# Power_Supply.net
KiCad netlist of a schematic drawn in Altium Designer
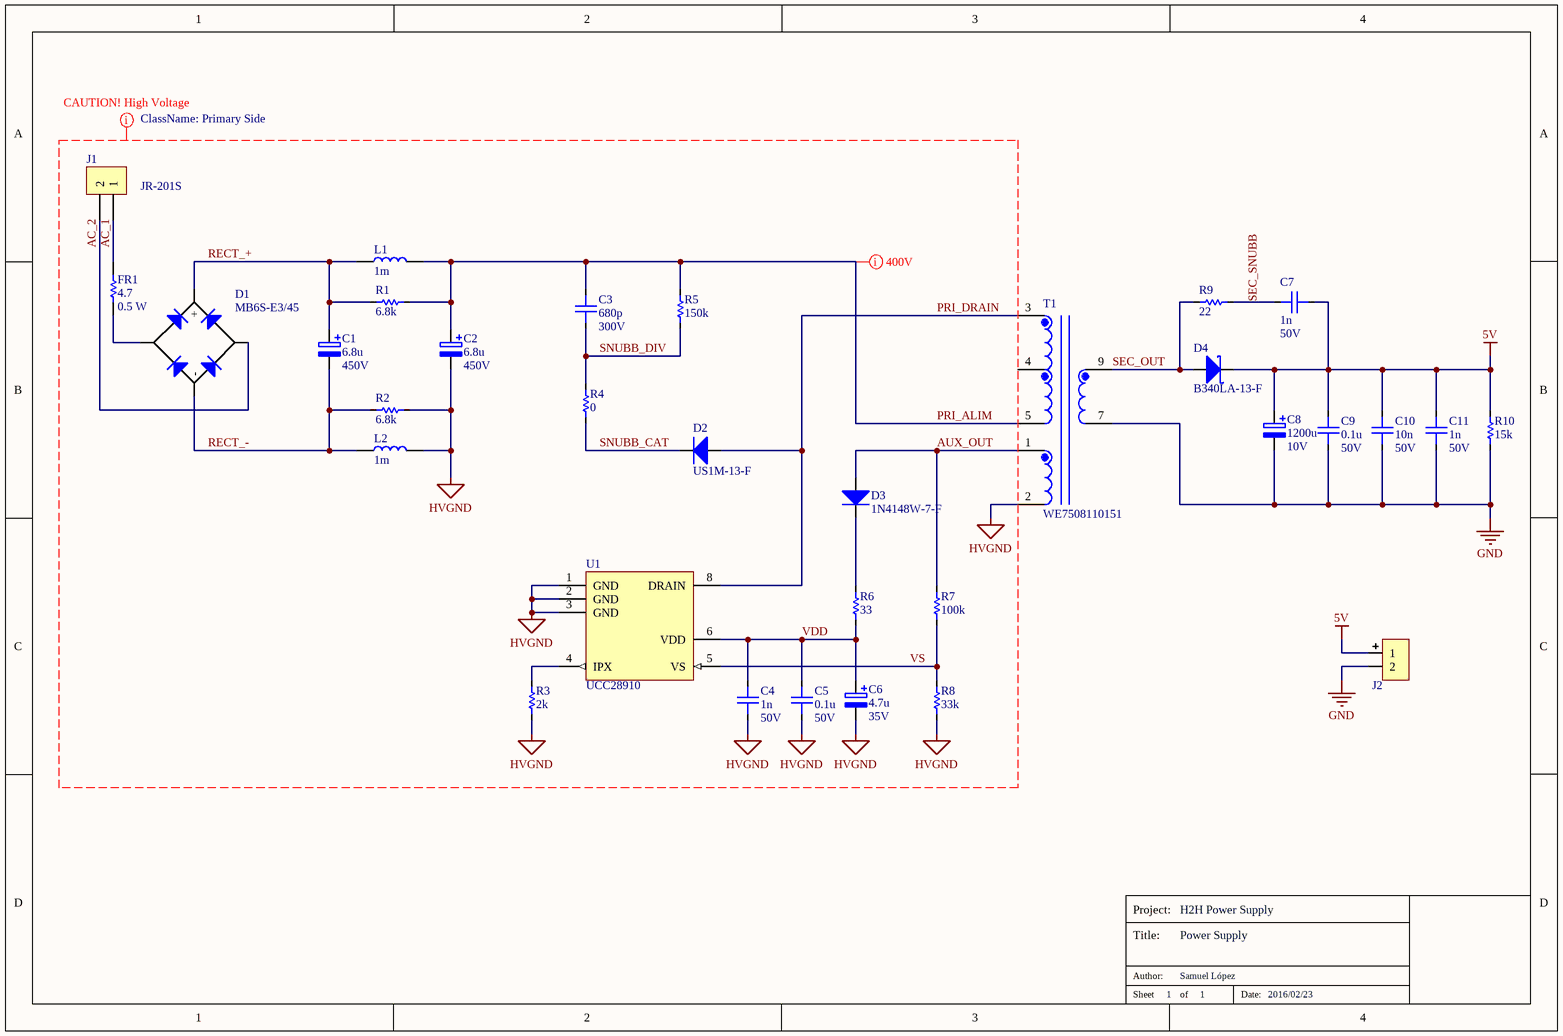
[diagram p0: Power Supply.SchDoc]

(export (version "E")
  (design (tool "Eeschema 10.0.6"))
  (components
    (comp (ref "C1")
      (value "6.8u")
      (footprint "450BXC6R8MEFC10X16")
      (description "Capacitor - Electrolytic Capacitor, 6.8 uF, 450 V, 20%, 10 mm")
      (fields (field (name "RATED VOLTAGE") "450V"))
      (libsource (lib "Supply") (part "450BXC6R8MEFC10X16"))
    )
    (comp (ref "C2")
      (value "6.8u")
      (footprint "450BXC6R8MEFC10X16")
      (description "Capacitor - Electrolytic Capacitor, 6.8 uF, 450 V, 20%, 10 mm")
      (fields (field (name "RATED VOLTAGE") "450V"))
      (libsource (lib "Supply") (part "450BXC6R8MEFC10X16"))
    )
    (comp (ref "C3")
      (value "680p")
      (footprint "C1206")
      (description "Capacitor")
      (fields (field (name "RATED VOLTAGE") "300V"))
      (libsource (lib "Misc") (part "Capacitor"))
    )
    (comp (ref "C4")
      (value "1n")
      (footprint "C1206")
      (description "Capacitor")
      (fields (field (name "RATED VOLTAGE") "50V"))
      (libsource (lib "Misc") (part "Capacitor"))
    )
    (comp (ref "C5")
      (value "0.1u")
      (footprint "C1206")
      (description "Capacitor")
      (fields (field (name "RATED VOLTAGE") "50V"))
      (libsource (lib "Misc") (part "Capacitor"))
    )
    (comp (ref "C6")
      (value "4.7u")
      (footprint "EXV475M035A9BAA")
      (description "Capacitor - Electrolytic Capacitor, SMD, 4.7 uF, 35 V, 4 mm")
      (fields (field (name "RATED VOLTAGE") "35V"))
      (libsource (lib "Supply") (part "EXV475M035A9BAA"))
    )
    (comp (ref "C7")
      (value "1n")
      (footprint "C1206")
      (description "Capacitor")
      (fields (field (name "RATED VOLTAGE") "50V"))
      (libsource (lib "Misc") (part "Capacitor"))
    )
    (comp (ref "C8")
      (value "1200u")
      (footprint "EEUFM1A122")
      (description "Capacitor - Electrolytic Capacitor, 1200 uF, 10 V, 20%, 10 mm")
      (fields (field (name "RATED VOLTAGE") "10V"))
      (libsource (lib "Supply") (part "EEUFM1A122"))
    )
    (comp (ref "C9")
      (value "0.1u")
      (footprint "C1206")
      (description "Capacitor")
      (fields (field (name "RATED VOLTAGE") "50V"))
      (libsource (lib "Misc") (part "Capacitor"))
    )
    (comp (ref "C10")
      (value "10n")
      (footprint "C1206")
      (description "Capacitor")
      (fields (field (name "RATED VOLTAGE") "50V"))
      (libsource (lib "Misc") (part "Capacitor"))
    )
    (comp (ref "C11")
      (value "1n")
      (footprint "C1206")
      (description "Capacitor")
      (fields (field (name "RATED VOLTAGE") "50V"))
      (libsource (lib "Misc") (part "Capacitor"))
    )
    (comp (ref "D1")
      (value "MB6S-E3/45")
      (footprint "MB6S-E3/45")
      (description "Diode - Bridge Rectifier, 600 V, 0.5 A")
      (libsource (lib "Supply") (part "MB6S-E3/45"))
    )
    (comp (ref "D2")
      (value "US1M-13-F")
      (footprint "US1M-13-F")
      (description "Diode - Ultra-fast, 75 ns, 1.7V, 1A, 1000V")
      (libsource (lib "Supply") (part "US1M-13-F"))
    )
    (comp (ref "D3")
      (value "1N4148W-7-F")
      (footprint "1N4148W-7-F")
      (description "Diode - Standard, Switch, 1.25V, 300mA, 100V")
      (libsource (lib "Supply") (part "1N4148W-7-F"))
    )
    (comp (ref "D4")
      (value "B340LA-13-F")
      (footprint "B340LA-13-F")
      (description "Diode - Schottky, 450mV, 3A, 40V")
      (libsource (lib "Supply") (part "B340LA-13-F"))
    )
    (comp (ref "FR1")
      (value "4.7")
      (footprint "NFR25H0004708JA500")
      (description "Resistor - Fusible, Non-flammable Resistor")
      (fields (field (name "POWER") "0.5 W"))
      (libsource (lib "Supply") (part "NFR25H0004708JA500"))
    )
    (comp (ref "J1")
      (value "JR-201S")
      (footprint "JR-201S")
      (description "Conn - 250 V AC, Inlet, IEC, Plug")
      (libsource (lib "Conn") (part "JR-201S"))
    )
    (comp (ref "J2")
      (value "JST PH 2 Pin")
      (footprint "B2B-PH-K-S")
      (description "Conn - Battery, Male, 2 Pin, PCB")
      (libsource (lib "Conn") (part "B2B-PH-K-S"))
    )
    (comp (ref "L1")
      (value "1m")
      (footprint "DR0810-105L")
      (description "Inductor - Power, 1 mH, 0.5 A Sat. Current, 10%")
      (libsource (lib "Supply") (part "DR0810-105L"))
    )
    (comp (ref "L2")
      (value "1m")
      (footprint "DR0810-105L")
      (description "Inductor - Power, 1 mH, 0.5 A Sat. Current, 10%")
      (libsource (lib "Supply") (part "DR0810-105L"))
    )
    (comp (ref "R1")
      (value "6.8k")
      (footprint "R1206")
      (description "Resistor")
      (libsource (lib "Misc") (part "Resistor"))
    )
    (comp (ref "R2")
      (value "6.8k")
      (footprint "R1206")
      (description "Resistor")
      (libsource (lib "Misc") (part "Resistor"))
    )
    (comp (ref "R3")
      (value "2k")
      (footprint "R1206")
      (description "Resistor")
      (libsource (lib "Misc") (part "Resistor"))
    )
    (comp (ref "R4")
      (value "0")
      (footprint "R1206")
      (description "Resistor")
      (libsource (lib "Misc") (part "Resistor"))
    )
    (comp (ref "R5")
      (value "150k")
      (footprint "R1206")
      (description "Resistor")
      (libsource (lib "Misc") (part "Resistor"))
    )
    (comp (ref "R6")
      (value "33")
      (footprint "R1206")
      (description "Resistor")
      (libsource (lib "Misc") (part "Resistor"))
    )
    (comp (ref "R7")
      (value "100k")
      (footprint "R1206")
      (description "Resistor")
      (libsource (lib "Misc") (part "Resistor"))
    )
    (comp (ref "R8")
      (value "33k")
      (footprint "R1206")
      (description "Resistor")
      (libsource (lib "Misc") (part "Resistor"))
    )
    (comp (ref "R9")
      (value "22")
      (footprint "R1206")
      (description "Resistor")
      (libsource (lib "Misc") (part "Resistor"))
    )
    (comp (ref "R10")
      (value "15k")
      (footprint "R1206")
      (description "Resistor")
      (libsource (lib "Misc") (part "Resistor"))
    )
    (comp (ref "T1")
      (value "WE7508110151")
      (footprint "WE7508110151")
      (description "Transformer - Flyback/Offline Transformer")
      (libsource (lib "Supply") (part "WE7508110151"))
    )
    (comp (ref "U1") (value "UCC28910") (footprint "UCC28910") (libsource (lib "Supply") (part "UCC28910")))
  )
  (nets
    (net (code "1") (name "/AC_1") (class "Default")
      (node (ref "FR1") (pin "1") (pinfunction "1_1") (pintype "passive"))
      (node (ref "J1") (pin "1") (pinfunction "1_1") (pintype "passive"))
    )
    (net (code "2") (name "/AC_2") (class "Default")
      (node (ref "D1") (pin "2") (pinfunction "AC_2") (pintype "passive"))
      (node (ref "J1") (pin "2") (pinfunction "2_2") (pintype "passive"))
    )
    (net (code "3") (name "/AUX_OUT") (class "Default")
      (node (ref "D3") (pin "1") (pinfunction "A_1") (pintype "passive"))
      (node (ref "R7") (pin "1") (pinfunction "1_1") (pintype "passive"))
      (node (ref "T1") (pin "1") (pinfunction "Aux1_1") (pintype "passive"))
    )
    (net (code "4") (name "/PRI_ALIM") (class "Default")
      (node (ref "C2") (pin "1") (pinfunction "1_1") (pintype "passive"))
      (node (ref "C3") (pin "1") (pinfunction "1_1") (pintype "passive"))
      (node (ref "L1") (pin "2") (pinfunction "2_2") (pintype "passive"))
      (node (ref "R1") (pin "2") (pinfunction "2_2") (pintype "passive"))
      (node (ref "R5") (pin "1") (pinfunction "1_1") (pintype "passive"))
      (node (ref "T1") (pin "5") (pinfunction "Pri3_5") (pintype "passive"))
    )
    (net (code "5") (name "/PRI_DRAIN") (class "Default")
      (node (ref "D2") (pin "1") (pinfunction "A_1") (pintype "passive"))
      (node (ref "T1") (pin "3") (pinfunction "Pri1_3") (pintype "passive"))
      (node (ref "U1") (pin "8") (pinfunction "DRAIN_8") (pintype "passive"))
    )
    (net (code "6") (name "/RECT_+") (class "Default")
      (node (ref "C1") (pin "1") (pinfunction "1_1") (pintype "passive"))
      (node (ref "D1") (pin "3") (pinfunction "+_3") (pintype "passive"))
      (node (ref "L1") (pin "1") (pinfunction "1_1") (pintype "passive"))
      (node (ref "R1") (pin "1") (pinfunction "1_1") (pintype "passive"))
    )
    (net (code "7") (name "/RECT_-") (class "Default")
      (node (ref "C1") (pin "2") (pinfunction "2_2") (pintype "passive"))
      (node (ref "D1") (pin "4") (pinfunction "-_4") (pintype "passive"))
      (node (ref "L2") (pin "1") (pinfunction "1_1") (pintype "passive"))
      (node (ref "R2") (pin "1") (pinfunction "1_1") (pintype "passive"))
    )
    (net (code "8") (name "/SEC_OUT") (class "Default")
      (node (ref "D4") (pin "1") (pinfunction "A_1") (pintype "passive"))
      (node (ref "R9") (pin "1") (pinfunction "1_1") (pintype "passive"))
      (node (ref "T1") (pin "9") (pinfunction "Sec1_9") (pintype "passive"))
    )
    (net (code "9") (name "/SEC_SNUBB") (class "Default")
      (node (ref "C7") (pin "1") (pinfunction "1_1") (pintype "passive"))
      (node (ref "R9") (pin "2") (pinfunction "2_2") (pintype "passive"))
    )
    (net (code "10") (name "/SNUBB_CAT") (class "Default")
      (node (ref "D2") (pin "2") (pinfunction "K_2") (pintype "passive"))
      (node (ref "R4") (pin "2") (pinfunction "2_2") (pintype "passive"))
    )
    (net (code "11") (name "/SNUBB_DIV") (class "Default")
      (node (ref "C3") (pin "2") (pinfunction "2_2") (pintype "passive"))
      (node (ref "R4") (pin "1") (pinfunction "1_1") (pintype "passive"))
      (node (ref "R5") (pin "2") (pinfunction "2_2") (pintype "passive"))
    )
    (net (code "12") (name "/VDD") (class "Default")
      (node (ref "C4") (pin "1") (pinfunction "1_1") (pintype "passive"))
      (node (ref "C5") (pin "1") (pinfunction "1_1") (pintype "passive"))
      (node (ref "C6") (pin "1") (pinfunction "1_1") (pintype "passive"))
      (node (ref "R6") (pin "2") (pinfunction "2_2") (pintype "passive"))
      (node (ref "U1") (pin "6") (pinfunction "VDD_6") (pintype "power_in"))
    )
    (net (code "13") (name "/VS") (class "Default")
      (node (ref "R7") (pin "2") (pinfunction "2_2") (pintype "passive"))
      (node (ref "R8") (pin "1") (pinfunction "1_1") (pintype "passive"))
      (node (ref "U1") (pin "5") (pinfunction "VS_5") (pintype "input"))
    )
    (net (code "14") (name "5V") (class "Default")
      (node (ref "C10") (pin "1") (pinfunction "1_1") (pintype "passive"))
      (node (ref "C11") (pin "1") (pinfunction "1_1") (pintype "passive"))
      (node (ref "C7") (pin "2") (pinfunction "2_2") (pintype "passive"))
      (node (ref "C8") (pin "1") (pinfunction "1_1") (pintype "passive"))
      (node (ref "C9") (pin "1") (pinfunction "1_1") (pintype "passive"))
      (node (ref "D4") (pin "2") (pinfunction "K_2") (pintype "passive"))
      (node (ref "J2") (pin "1") (pinfunction "1_1") (pintype "passive"))
      (node (ref "R10") (pin "1") (pinfunction "1_1") (pintype "passive"))
    )
    (net (code "15") (name "GND") (class "Default")
      (node (ref "C10") (pin "2") (pinfunction "2_2") (pintype "passive"))
      (node (ref "C11") (pin "2") (pinfunction "2_2") (pintype "passive"))
      (node (ref "C8") (pin "2") (pinfunction "2_2") (pintype "passive"))
      (node (ref "C9") (pin "2") (pinfunction "2_2") (pintype "passive"))
      (node (ref "J2") (pin "2") (pinfunction "2_2") (pintype "passive"))
      (node (ref "R10") (pin "2") (pinfunction "2_2") (pintype "passive"))
      (node (ref "T1") (pin "7") (pinfunction "Sec2_7") (pintype "passive"))
    )
    (net (code "16") (name "HVGND") (class "Default")
      (node (ref "C2") (pin "2") (pinfunction "2_2") (pintype "passive"))
      (node (ref "C4") (pin "2") (pinfunction "2_2") (pintype "passive"))
      (node (ref "C5") (pin "2") (pinfunction "2_2") (pintype "passive"))
      (node (ref "C6") (pin "2") (pinfunction "2_2") (pintype "passive"))
      (node (ref "L2") (pin "2") (pinfunction "2_2") (pintype "passive"))
      (node (ref "R2") (pin "2") (pinfunction "2_2") (pintype "passive"))
      (node (ref "R3") (pin "2") (pinfunction "2_2") (pintype "passive"))
      (node (ref "R8") (pin "2") (pinfunction "2_2") (pintype "passive"))
      (node (ref "T1") (pin "2") (pinfunction "Aux2_2") (pintype "passive"))
      (node (ref "U1") (pin "1") (pinfunction "GND_1") (pintype "power_in"))
      (node (ref "U1") (pin "2") (pinfunction "GND_2") (pintype "power_in"))
      (node (ref "U1") (pin "3") (pinfunction "GND_3") (pintype "power_in"))
    )
    (net (code "17") (name "Net-(D1-AC-Pad1)") (class "Default")
      (node (ref "D1") (pin "1") (pinfunction "AC_1") (pintype "passive"))
      (node (ref "FR1") (pin "2") (pinfunction "2_2") (pintype "passive"))
    )
    (net (code "18") (name "Net-(D3-K)") (class "Default")
      (node (ref "D3") (pin "2") (pinfunction "K_2") (pintype "passive"))
      (node (ref "R6") (pin "1") (pinfunction "1_1") (pintype "passive"))
    )
    (net (code "19") (name "Net-(U1-IPX)") (class "Default")
      (node (ref "R3") (pin "1") (pinfunction "1_1") (pintype "passive"))
      (node (ref "U1") (pin "4") (pinfunction "IPX_4") (pintype "output"))
    )
    (net (code "20") (name "unconnected-(T1-Pri2-Pad4)") (class "Default")
      (node (ref "T1") (pin "4") (pinfunction "Pri2_4") (pintype "passive"))
    )
  )
)
